# PROC010B_XDS110_Interface_1A.net
KiCad netlist of a schematic drawn in Altium Designer
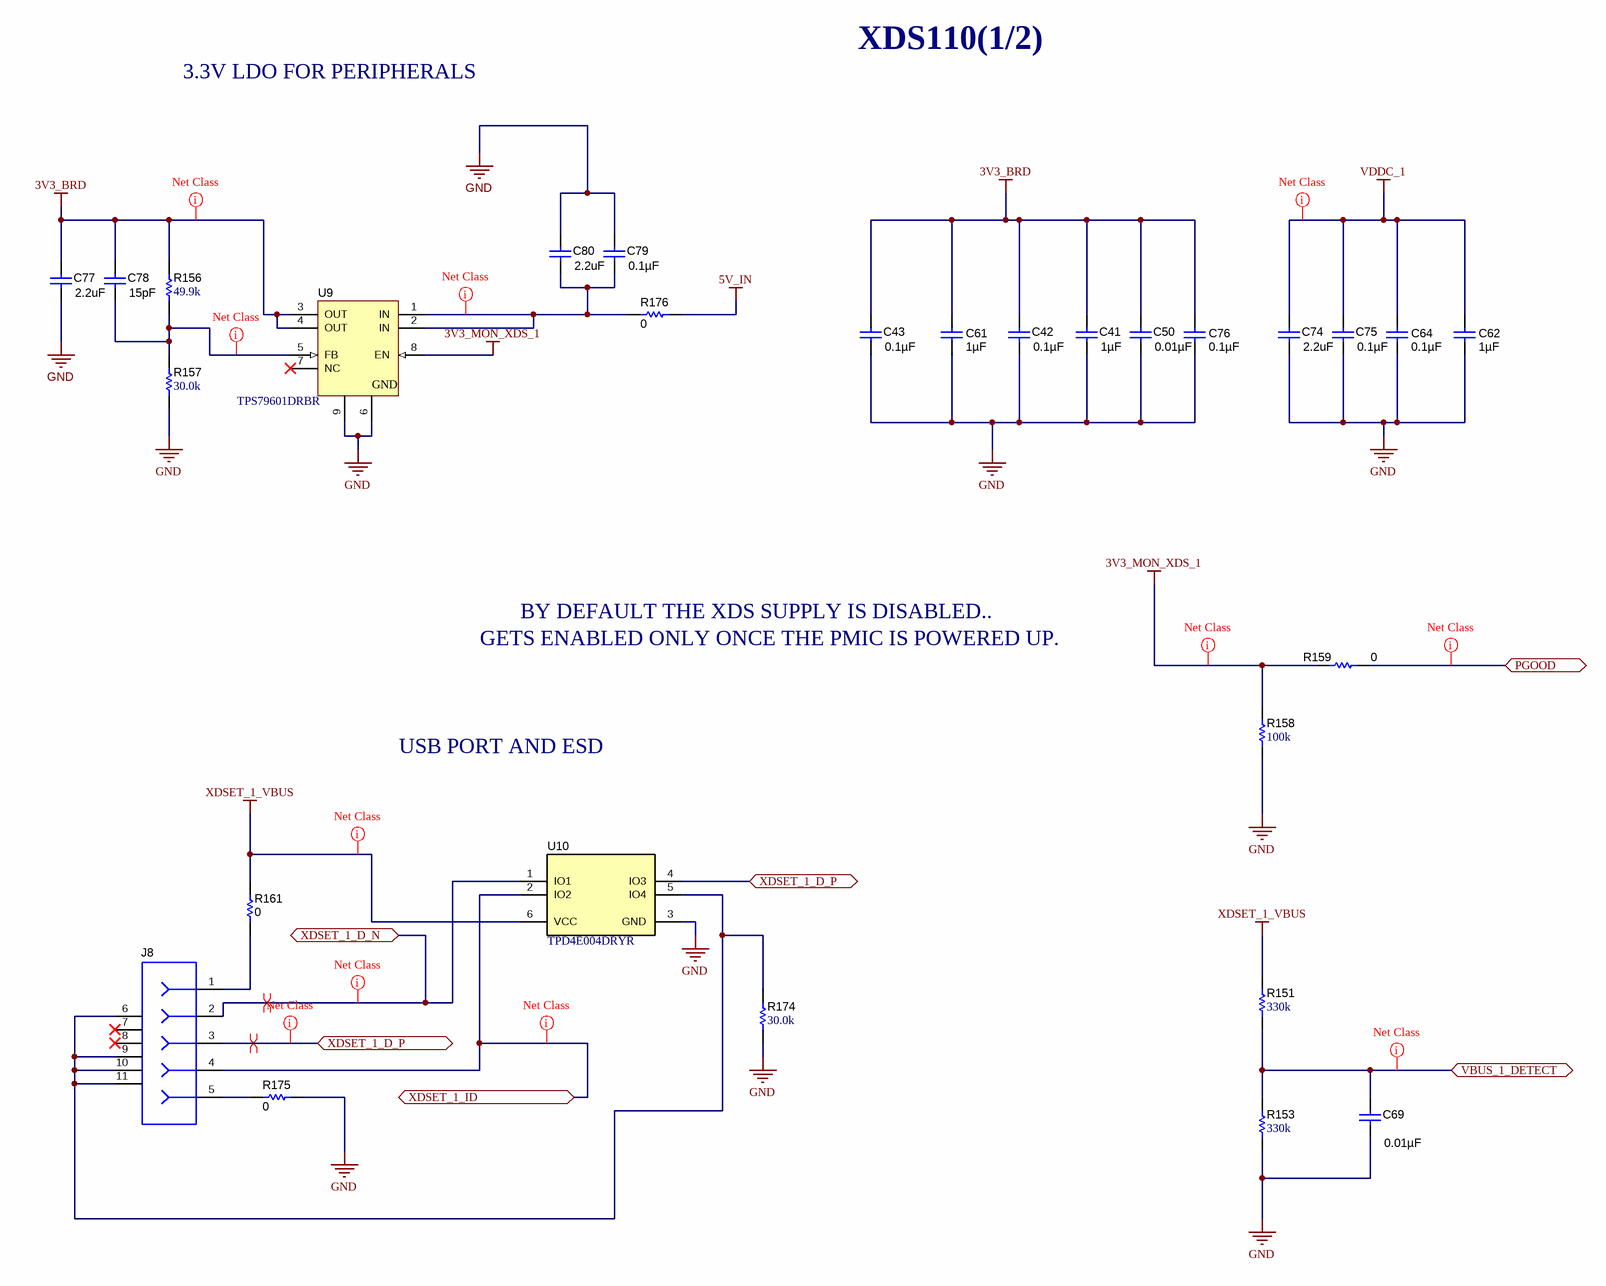
[diagram p0: PROC010B_XDS110 Interface_1A.SchDoc]

(export (version "E")
  (design (tool "Eeschema 10.0.6"))
  (components
    (comp (ref "C41")
      (value "C1005X7S0J105M050BC")
      (footprint "0402L")
      (description "CAP, CERM, 1 µF, 6.3 V,+/- 20%, X7S, 0402")
      (fields (field (name "MANUFACTURER") "TDK") (field (name "VALUEDISPLAYED") "1µF"))
      (libsource (lib "Altium Vault - TI") (part "Capacitor"))
    )
    (comp (ref "C42")
      (value "C0402C104K8RACTU")
      (footprint "0402L")
      (description "CAP, CERM, 0.1 µF, 10 V,+/- 10%, X7R, 0402")
      (fields (field (name "MANUFACTURER") "Kemet") (field (name "VALUEDISPLAYED") "0.1µF"))
      (libsource (lib "Altium Vault - TI") (part "Capacitor"))
    )
    (comp (ref "C43")
      (value "C0402C104K8RACTU")
      (footprint "0402L")
      (description "CAP, CERM, 0.1 µF, 10 V,+/- 10%, X7R, 0402")
      (fields (field (name "MANUFACTURER") "Kemet") (field (name "VALUEDISPLAYED") "0.1µF"))
      (libsource (lib "Altium Vault - TI") (part "Capacitor"))
    )
    (comp (ref "C50")
      (value "C1005X7R1E103K050BB")
      (footprint "0402L")
      (description "CAP, CERM, 0.01 µF, 25 V,+/- 10%, X7R, 0402")
      (fields (field (name "MANUFACTURER") "TDK") (field (name "VALUEDISPLAYED") "0.01µF"))
      (libsource (lib "Altium Vault - TI") (part "Capacitor"))
    )
    (comp (ref "C61")
      (value "C1005X7S0J105M050BC")
      (footprint "0402L")
      (description "CAP, CERM, 1 µF, 6.3 V,+/- 20%, X7S, 0402")
      (fields (field (name "MANUFACTURER") "TDK") (field (name "VALUEDISPLAYED") "1µF"))
      (libsource (lib "Altium Vault - TI") (part "Capacitor"))
    )
    (comp (ref "C62")
      (value "C1005X7S0J105M050BC")
      (footprint "0402L")
      (description "CAP, CERM, 1 µF, 6.3 V,+/- 20%, X7S, 0402")
      (fields (field (name "MANUFACTURER") "TDK") (field (name "VALUEDISPLAYED") "1µF"))
      (libsource (lib "Altium Vault - TI") (part "Capacitor"))
    )
    (comp (ref "C64")
      (value "C0402C104K8RACTU")
      (footprint "0402L")
      (description "CAP, CERM, 0.1 µF, 10 V,+/- 10%, X7R, 0402")
      (fields (field (name "MANUFACTURER") "Kemet") (field (name "VALUEDISPLAYED") "0.1µF"))
      (libsource (lib "Altium Vault - TI") (part "Capacitor"))
    )
    (comp (ref "C69")
      (value "C0402C103K4RACTU")
      (footprint "0402L")
      (description "CAP, CERM, 0.01 µF, 16 V,+/- 10%, X7R, 0402")
      (fields (field (name "MANUFACTURER") "Kemet") (field (name "VALUEDISPLAYED") "0.01µF"))
      (libsource (lib "Altium Vault - TI") (part "Capacitor"))
    )
    (comp (ref "C74")
      (value "C1005X7S1A225K050BC")
      (footprint "0402_065L")
      (description "CAP, CERM, 2.2 uF, 10 V, +/- 10%, X7S, 0402")
      (fields
        (field (name "MANUFACTURER") "TDK")
        (field (name "VALUEDISPLAYED") "2.2uF")
        (field (name "PUBLISHER") "Texas Instruments")
      )
      (libsource (lib "Altium Vault - TI") (part "CMP-0006302-2"))
    )
    (comp (ref "C75")
      (value "C0402C104K8RACTU")
      (footprint "0402L")
      (description "CAP, CERM, 0.1 µF, 10 V,+/- 10%, X7R, 0402")
      (fields (field (name "MANUFACTURER") "Kemet") (field (name "VALUEDISPLAYED") "0.1µF"))
      (libsource (lib "Altium Vault - TI") (part "Capacitor"))
    )
    (comp (ref "C76")
      (value "C0402C104K8RACTU")
      (footprint "0402L")
      (description "CAP, CERM, 0.1 µF, 10 V,+/- 10%, X7R, 0402")
      (fields (field (name "MANUFACTURER") "Kemet") (field (name "VALUEDISPLAYED") "0.1µF"))
      (libsource (lib "Altium Vault - TI") (part "Capacitor"))
    )
    (comp (ref "C77")
      (value "C1005X7S1A225K050BC")
      (footprint "0402_065L")
      (description "CAP, CERM, 2.2 uF, 10 V, +/- 10%, X7S, 0402")
      (fields
        (field (name "MANUFACTURER") "TDK")
        (field (name "VALUEDISPLAYED") "2.2uF")
        (field (name "PUBLISHER") "Texas Instruments")
      )
      (libsource (lib "Altium Vault - TI") (part "CMP-0006302-2"))
    )
    (comp (ref "C78")
      (value "04025A150FAT2A")
      (footprint "0402L")
      (description "CAP, CERM, 15 pF, 50 V,+/- 1%, C0G/NP0, 0402")
      (fields (field (name "MANUFACTURER") "AVX") (field (name "VALUEDISPLAYED") "15pF"))
      (libsource (lib "Altium Vault - TI") (part "Capacitor"))
    )
    (comp (ref "C79")
      (value "C0402C104K8RACTU")
      (footprint "0402L")
      (description "CAP, CERM, 0.1 µF, 10 V,+/- 10%, X7R, 0402")
      (fields (field (name "MANUFACTURER") "Kemet") (field (name "VALUEDISPLAYED") "0.1µF"))
      (libsource (lib "Altium Vault - TI") (part "Capacitor"))
    )
    (comp (ref "C80")
      (value "C1005X7S1A225K050BC")
      (footprint "0402_065L")
      (description "CAP, CERM, 2.2 uF, 10 V, +/- 10%, X7S, 0402")
      (fields
        (field (name "MANUFACTURER") "TDK")
        (field (name "VALUEDISPLAYED") "2.2uF")
        (field (name "PUBLISHER") "Texas Instruments")
      )
      (libsource (lib "Altium Vault - TI") (part "CMP-0006302-2"))
    )
    (comp (ref "J8")
      (value "105017-0001")
      (footprint "CONN_105017-0001")
      (description "Connector, Receptacle, Micro-USB Type B, R/A, Bottom Mount SMT")
      (fields (field (name "MANUFACTURER") "Molex") (field (name "PUBLISHER") "Texas Instruments"))
      (libsource (lib "Altium Vault - TI") (part "CONN_105017-0001"))
    )
    (comp (ref "R151")
      (value "CRCW0402330KFKED")
      (footprint "0402L")
      (description "RES, 330 k, 1%, 0.063 W, AEC-Q200 Grade 0, 0402")
      (fields (field (name "MANUFACTURER") "Vishay-Dale") (field (name "VALUEDISPLAYED") "330k"))
      (libsource (lib "Altium Vault - TI") (part "Resistor"))
    )
    (comp (ref "R153")
      (value "CRCW0402330KFKED")
      (footprint "0402L")
      (description "RES, 330 k, 1%, 0.063 W, AEC-Q200 Grade 0, 0402")
      (fields (field (name "MANUFACTURER") "Vishay-Dale") (field (name "VALUEDISPLAYED") "330k"))
      (libsource (lib "Altium Vault - TI") (part "Resistor"))
    )
    (comp (ref "R156")
      (value "CRCW040249K9FKED")
      (footprint "0402L")
      (description "RES, 49.9 k, 1%, 0.063 W, AEC-Q200 Grade 0, 0402")
      (fields (field (name "MANUFACTURER") "Vishay-Dale") (field (name "VALUEDISPLAYED") "49.9k"))
      (libsource (lib "Altium Vault - TI") (part "Resistor"))
    )
    (comp (ref "R157")
      (value "CRCW040230K0FKED")
      (footprint "0402L")
      (description "RES, 30.0 k, 1%, 0.063 W, AEC-Q200 Grade 0, 0402")
      (fields (field (name "MANUFACTURER") "Vishay-Dale") (field (name "VALUEDISPLAYED") "30.0k"))
      (libsource (lib "Altium Vault - TI") (part "Resistor"))
    )
    (comp (ref "R158")
      (value "CRCW0402100KFKED")
      (footprint "0402L")
      (description "RES, 100 k, 1%, 0.063 W, AEC-Q200 Grade 0, 0402")
      (fields (field (name "MANUFACTURER") "Vishay-Dale") (field (name "VALUEDISPLAYED") "100k"))
      (libsource (lib "Altium Vault - TI") (part "Resistor"))
    )
    (comp (ref "R159")
      (value "ERJ-2GE0R00X")
      (footprint "0402L")
      (description "RES, 0, 5%, 0.063 W, 0402")
      (fields
        (field (name "MANUFACTURER") "Panasonic")
        (field (name "VALUEDISPLAYED") "0")
        (field (name "PUBLISHER") "Texas Instruments")
      )
      (libsource (lib "Altium Vault - TI") (part "Resistor"))
    )
    (comp (ref "R161")
      (value "MCT06030Z0000ZP500")
      (footprint "0603")
      (description "RES, 0, 5%, 0.125 W, 0603")
      (fields
        (field (name "MANUFACTURER") "Vishay/Beyschlag")
        (field (name "VALUEDISPLAYED") "0")
        (field (name "PUBLISHER") "Texas Instruments")
      )
      (libsource (lib "Altium Vault - TI") (part "Resistor"))
    )
    (comp (ref "R174")
      (value "CRCW040230K0FKED")
      (footprint "0402L")
      (description "RES, 30.0 k, 1%, 0.063 W, AEC-Q200 Grade 0, 0402")
      (fields (field (name "MANUFACTURER") "Vishay-Dale") (field (name "VALUEDISPLAYED") "30.0k"))
      (libsource (lib "Altium Vault - TI") (part "Resistor"))
    )
    (comp (ref "R175")
      (value "MCT06030Z0000ZP500")
      (footprint "0603")
      (description "RES, 0, 5%, 0.125 W, 0603")
      (fields
        (field (name "MANUFACTURER") "Vishay/Beyschlag")
        (field (name "VALUEDISPLAYED") "0")
        (field (name "PUBLISHER") "Texas Instruments")
      )
      (libsource (lib "Altium Vault - TI") (part "Resistor"))
    )
    (comp (ref "R176")
      (value "MCT06030Z0000ZP500")
      (footprint "0603")
      (description "RES, 0, 5%, 0.125 W, 0603")
      (fields
        (field (name "MANUFACTURER") "Vishay/Beyschlag")
        (field (name "VALUEDISPLAYED") "0")
        (field (name "PUBLISHER") "Texas Instruments")
      )
      (libsource (lib "Altium Vault - TI") (part "Resistor"))
    )
    (comp (ref "U9")
      (value "TPS79601DRBR")
      (footprint "DRB0008B")
      (fields (field (name "MANUFACTURER") "Texas Instruments") (field (name "PARTNUMBER") "TPS79601DRBR"))
      (libsource (lib "Altium Vault - TI") (part "CMP-0036402-3"))
    )
    (comp (ref "U10")
      (value "TPD4E004DRYR")
      (footprint "DRY0006A")
      (fields (field (name "MANUFACTURER") "Texas Instruments") (field (name "PARTNUMBER") "TPD4E004DRYR"))
      (libsource (lib "Altium Vault - TI") (part "CMP-0043115-2"))
    )
  )
  (nets
    (net (code "1") (name "/PGOOD") (class "Default")
      (node (ref "R159") (pin "1") (pinfunction "1_1") (pintype "passive"))
    )
    (net (code "2") (name "/VBUS_1_DETECT") (class "Default")
      (node (ref "C69") (pin "2") (pinfunction "2_2") (pintype "passive"))
      (node (ref "R151") (pin "1") (pinfunction "1_1") (pintype "passive"))
      (node (ref "R153") (pin "2") (pinfunction "2_2") (pintype "passive"))
    )
    (net (code "3") (name "/XDSET_1_D_N") (class "Default")
      (node (ref "J8") (pin "2") (pintype "passive"))
      (node (ref "U10") (pin "1") (pinfunction "IO1_1") (pintype "passive"))
    )
    (net (code "4") (name "/XDSET_1_D_P") (class "Default")
      (node (ref "J8") (pin "3") (pintype "passive"))
      (node (ref "U10") (pin "4") (pinfunction "IO3_4") (pintype "passive"))
    )
    (net (code "5") (name "/XDSET_1_ID") (class "Default")
      (node (ref "J8") (pin "4") (pintype "passive"))
      (node (ref "U10") (pin "2") (pinfunction "IO2_2") (pintype "passive"))
    )
    (net (code "6") (name "3V3_BRD") (class "Default")
      (node (ref "C41") (pin "2") (pinfunction "2_2") (pintype "passive"))
      (node (ref "C42") (pin "2") (pinfunction "2_2") (pintype "passive"))
      (node (ref "C43") (pin "2") (pinfunction "2_2") (pintype "passive"))
      (node (ref "C50") (pin "2") (pinfunction "2_2") (pintype "passive"))
      (node (ref "C61") (pin "2") (pinfunction "2_2") (pintype "passive"))
      (node (ref "C76") (pin "2") (pinfunction "2_2") (pintype "passive"))
      (node (ref "C77") (pin "2") (pinfunction "2_2") (pintype "passive"))
      (node (ref "C78") (pin "2") (pinfunction "2_2") (pintype "passive"))
      (node (ref "R156") (pin "2") (pinfunction "2_2") (pintype "passive"))
      (node (ref "U9") (pin "3") (pinfunction "OUT_3") (pintype "power_in"))
      (node (ref "U9") (pin "4") (pinfunction "OUT_4") (pintype "power_in"))
    )
    (net (code "7") (name "3V3_MON_XDS_1") (class "Default")
      (node (ref "R158") (pin "2") (pinfunction "2_2") (pintype "passive"))
      (node (ref "R159") (pin "2") (pinfunction "2_2") (pintype "passive"))
      (node (ref "U9") (pin "8") (pinfunction "EN_8") (pintype "input"))
    )
    (net (code "8") (name "5V_IN") (class "Default")
      (node (ref "R176") (pin "2") (pinfunction "2_2") (pintype "passive"))
    )
    (net (code "9") (name "GND") (class "Default")
      (node (ref "C41") (pin "1") (pinfunction "1_1") (pintype "passive"))
      (node (ref "C42") (pin "1") (pinfunction "1_1") (pintype "passive"))
      (node (ref "C43") (pin "1") (pinfunction "1_1") (pintype "passive"))
      (node (ref "C50") (pin "1") (pinfunction "1_1") (pintype "passive"))
      (node (ref "C61") (pin "1") (pinfunction "1_1") (pintype "passive"))
      (node (ref "C62") (pin "1") (pinfunction "1_1") (pintype "passive"))
      (node (ref "C64") (pin "1") (pinfunction "1_1") (pintype "passive"))
      (node (ref "C69") (pin "1") (pinfunction "1_1") (pintype "passive"))
      (node (ref "C74") (pin "1") (pinfunction "1_1") (pintype "passive"))
      (node (ref "C75") (pin "1") (pinfunction "1_1") (pintype "passive"))
      (node (ref "C76") (pin "1") (pinfunction "1_1") (pintype "passive"))
      (node (ref "C77") (pin "1") (pinfunction "1_1") (pintype "passive"))
      (node (ref "C79") (pin "1") (pinfunction "1_1") (pintype "passive"))
      (node (ref "C80") (pin "1") (pinfunction "1_1") (pintype "passive"))
      (node (ref "R153") (pin "1") (pinfunction "1_1") (pintype "passive"))
      (node (ref "R157") (pin "1") (pinfunction "1_1") (pintype "passive"))
      (node (ref "R158") (pin "1") (pinfunction "1_1") (pintype "passive"))
      (node (ref "R174") (pin "1") (pinfunction "1_1") (pintype "passive"))
      (node (ref "R175") (pin "1") (pinfunction "1_1") (pintype "passive"))
      (node (ref "U10") (pin "3") (pinfunction "GND_3") (pintype "power_in"))
      (node (ref "U9") (pin "6") (pinfunction "GND_6") (pintype "power_in"))
      (node (ref "U9") (pin "9") (pinfunction "GND_9") (pintype "power_in"))
    )
    (net (code "10") (name "Net-(C79-Pad2)") (class "Default")
      (node (ref "C79") (pin "2") (pinfunction "2_2") (pintype "passive"))
      (node (ref "C80") (pin "2") (pinfunction "2_2") (pintype "passive"))
      (node (ref "R176") (pin "1") (pinfunction "1_1") (pintype "passive"))
      (node (ref "U9") (pin "1") (pinfunction "IN_1") (pintype "power_in"))
      (node (ref "U9") (pin "2") (pinfunction "IN_2") (pintype "power_in"))
    )
    (net (code "11") (name "Net-(J8-Pad1)") (class "Default")
      (node (ref "J8") (pin "1") (pintype "passive"))
      (node (ref "R161") (pin "1") (pinfunction "1_1") (pintype "passive"))
    )
    (net (code "12") (name "Net-(J8-Pad5)") (class "Default")
      (node (ref "J8") (pin "5") (pintype "passive"))
      (node (ref "R175") (pin "2") (pinfunction "2_2") (pintype "passive"))
    )
    (net (code "13") (name "Net-(U9-FB)") (class "Default")
      (node (ref "C78") (pin "1") (pinfunction "1_1") (pintype "passive"))
      (node (ref "R156") (pin "1") (pinfunction "1_1") (pintype "passive"))
      (node (ref "R157") (pin "2") (pinfunction "2_2") (pintype "passive"))
      (node (ref "U9") (pin "5") (pinfunction "FB_5") (pintype "input"))
    )
    (net (code "14") (name "Net-(U10-IO4)") (class "Default")
      (node (ref "J8") (pin "10") (pintype "passive"))
      (node (ref "J8") (pin "11") (pintype "passive"))
      (node (ref "J8") (pin "6") (pintype "passive"))
      (node (ref "J8") (pin "9") (pintype "passive"))
      (node (ref "R174") (pin "2") (pinfunction "2_2") (pintype "passive"))
      (node (ref "U10") (pin "5") (pinfunction "IO4_5") (pintype "passive"))
    )
    (net (code "15") (name "VDDC_1") (class "Default")
      (node (ref "C62") (pin "2") (pinfunction "2_2") (pintype "passive"))
      (node (ref "C64") (pin "2") (pinfunction "2_2") (pintype "passive"))
      (node (ref "C74") (pin "2") (pinfunction "2_2") (pintype "passive"))
      (node (ref "C75") (pin "2") (pinfunction "2_2") (pintype "passive"))
    )
    (net (code "16") (name "XDSET_1_VBUS") (class "Default")
      (node (ref "R151") (pin "2") (pinfunction "2_2") (pintype "passive"))
      (node (ref "R161") (pin "2") (pinfunction "2_2") (pintype "passive"))
      (node (ref "U10") (pin "6") (pinfunction "VCC_6") (pintype "power_in"))
    )
    (net (code "17") (name "unconnected-(J8-Pad7)") (class "Default")
      (node (ref "J8") (pin "7") (pintype "passive+no_connect"))
    )
    (net (code "18") (name "unconnected-(J8-Pad8)") (class "Default")
      (node (ref "J8") (pin "8") (pintype "passive+no_connect"))
    )
    (net (code "19") (name "unconnected-(U9-NC-Pad7)") (class "Default")
      (node (ref "U9") (pin "7") (pinfunction "NC_7") (pintype "passive+no_connect"))
    )
  )
)
